# dashbutton_2450_v3.net
KiCad netlist of a schematic drawn in EAGLE
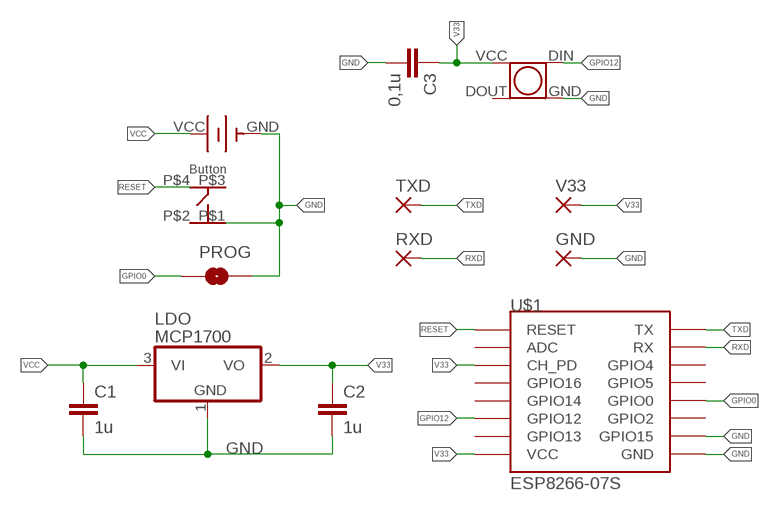
[diagram p0: schematic, sheet 1]

(export (version "E")
  (design (tool "Eeschema 10.0.6"))
  (components
    (comp (ref "BUTTON")
      (value "OMRON_B3FS_BUTTON")
      (footprint "eagle-import:BUTTON_OMRON_B3FS")
      (libsource (lib "eagle-import") (part "OMRON_B3FS_BUTTON"))
    )
    (comp (ref "C1")
      (value "1u")
      (footprint "eagle-import:C1206")
      (libsource (lib "eagle-import") (part "C-EUC1206"))
    )
    (comp (ref "C2")
      (value "1u")
      (footprint "eagle-import:C1206")
      (libsource (lib "eagle-import") (part "C-EUC1206"))
    )
    (comp (ref "C3")
      (value "0,1u")
      (footprint "eagle-import:C1206")
      (libsource (lib "eagle-import") (part "C-EUC1206"))
    )
    (comp (ref "GND")
      (value "WIREPADSMD1,27-254")
      (footprint "eagle-import:SMD1,27-2,54")
      (libsource (lib "eagle-import") (part "WIREPADSMD1,27-254"))
    )
    (comp (ref "LDO")
      (value "MCP1700")
      (footprint "eagle-import:SOT23")
      (libsource (lib "eagle-import") (part "MCP1703CB"))
    )
    (comp (ref "PROG")
      (value "JUMPER-SMT_2_NO_NO-SILK")
      (footprint "eagle-import:SMT-JUMPER_2_NO_NO-SILK")
      (libsource (lib "eagle-import") (part "JUMPER-SMT_2_NO_NO-SILK"))
    )
    (comp (ref "RXD")
      (value "WIREPADSMD1,27-254")
      (footprint "eagle-import:SMD1,27-2,54")
      (libsource (lib "eagle-import") (part "WIREPADSMD1,27-254"))
    )
    (comp (ref "TXD")
      (value "WIREPADSMD1,27-254")
      (footprint "eagle-import:SMD1,27-2,54")
      (libsource (lib "eagle-import") (part "WIREPADSMD1,27-254"))
    )
    (comp (ref "U$1")
      (value "ESP8266-07S")
      (footprint "eagle-import:ESP8266-07S")
      (libsource (lib "eagle-import") (part "ESP8266-07S"))
    )
    (comp (ref "U$2")
      (value "2450_BATTERYHOLDER_SMD")
      (footprint "eagle-import:2450_BATTERYHOLDER_SMD")
      (libsource (lib "eagle-import") (part "2450_BATTERYHOLDER_SMD"))
    )
    (comp (ref "U$3")
      (value "WS2812B")
      (footprint "eagle-import:WS2812B")
      (libsource (lib "eagle-import") (part "WS2812B"))
    )
    (comp (ref "V33")
      (value "WIREPADSMD1,27-254")
      (footprint "eagle-import:SMD1,27-2,54")
      (libsource (lib "eagle-import") (part "WIREPADSMD1,27-254"))
    )
  )
  (nets
    (net (code "1") (name "GND") (class "Default")
      (node (ref "BUTTON") (pin "P$1") (pinfunction "P1_P$1") (pintype "bidirectional"))
      (node (ref "C1") (pin "2") (pinfunction "2_2") (pintype "passive"))
      (node (ref "C2") (pin "2") (pinfunction "2_2") (pintype "passive"))
      (node (ref "C3") (pin "2") (pinfunction "2_2") (pintype "passive"))
      (node (ref "GND") (pin "1") (pinfunction "P_1") (pintype "passive"))
      (node (ref "LDO") (pin "1") (pinfunction "GND_1") (pintype "passive"))
      (node (ref "PROG") (pin "2") (pinfunction "2_2") (pintype "passive"))
      (node (ref "U$1") (pin "GND") (pinfunction "GND_GND") (pintype "bidirectional"))
      (node (ref "U$1") (pin "GPIO15") (pinfunction "GPIO15_GPIO15") (pintype "bidirectional"))
      (node (ref "U$2") (pin "GND") (pinfunction "GND_GND") (pintype "bidirectional"))
      (node (ref "U$3") (pin "GND") (pinfunction "GND_GND") (pintype "bidirectional"))
    )
    (net (code "2") (name "GPIO0") (class "Default")
      (node (ref "PROG") (pin "1") (pinfunction "1_1") (pintype "passive"))
      (node (ref "U$1") (pin "GPIO0") (pinfunction "GPIO0_GPIO0") (pintype "bidirectional"))
    )
    (net (code "3") (name "GPIO12") (class "Default")
      (node (ref "U$1") (pin "GPIO12") (pinfunction "GPIO12_GPIO12") (pintype "bidirectional"))
      (node (ref "U$3") (pin "DIN") (pinfunction "DIN_DIN") (pintype "bidirectional"))
    )
    (net (code "4") (name "RESET") (class "Default")
      (node (ref "BUTTON") (pin "P$4") (pinfunction "P4_P$4") (pintype "bidirectional"))
      (node (ref "U$1") (pin "RST") (pinfunction "RESET_RST") (pintype "bidirectional"))
    )
    (net (code "5") (name "RXD") (class "Default")
      (node (ref "RXD") (pin "1") (pinfunction "P_1") (pintype "passive"))
      (node (ref "U$1") (pin "RXD") (pinfunction "RX_RXD") (pintype "bidirectional"))
    )
    (net (code "6") (name "TXD") (class "Default")
      (node (ref "TXD") (pin "1") (pinfunction "P_1") (pintype "passive"))
      (node (ref "U$1") (pin "TXD") (pinfunction "TX_TXD") (pintype "bidirectional"))
    )
    (net (code "7") (name "V33") (class "Default")
      (node (ref "C2") (pin "1") (pinfunction "1_1") (pintype "passive"))
      (node (ref "C3") (pin "1") (pinfunction "1_1") (pintype "passive"))
      (node (ref "LDO") (pin "2") (pinfunction "VO_2") (pintype "passive"))
      (node (ref "U$1") (pin "EN") (pinfunction "CH_PD_EN") (pintype "bidirectional"))
      (node (ref "U$1") (pin "VCC") (pinfunction "VCC_VCC") (pintype "bidirectional"))
      (node (ref "U$3") (pin "VCC") (pinfunction "VCC_VCC") (pintype "bidirectional"))
      (node (ref "V33") (pin "1") (pinfunction "P_1") (pintype "passive"))
    )
    (net (code "8") (name "VCC") (class "Default")
      (node (ref "C1") (pin "1") (pinfunction "1_1") (pintype "passive"))
      (node (ref "LDO") (pin "3") (pinfunction "VI_3") (pintype "input"))
      (node (ref "U$2") (pin "VCC") (pinfunction "VCC_VCC") (pintype "bidirectional"))
    )
    (net (code "9") (name "unconnected-(BUTTON-P2-PadP$2)") (class "Default")
      (node (ref "BUTTON") (pin "P$2") (pinfunction "P2_P$2") (pintype "bidirectional"))
    )
    (net (code "10") (name "unconnected-(BUTTON-P3-PadP$3)") (class "Default")
      (node (ref "BUTTON") (pin "P$3") (pinfunction "P3_P$3") (pintype "bidirectional"))
    )
    (net (code "11") (name "unconnected-(U$1-PadADC)") (class "Default")
      (node (ref "U$1") (pin "ADC") (pinfunction "ADC_ADC") (pintype "bidirectional"))
    )
    (net (code "12") (name "unconnected-(U$1-PadGPIO2)") (class "Default")
      (node (ref "U$1") (pin "GPIO2") (pinfunction "GPIO2_GPIO2") (pintype "bidirectional"))
    )
    (net (code "13") (name "unconnected-(U$1-PadGPIO4)") (class "Default")
      (node (ref "U$1") (pin "GPIO4") (pinfunction "GPIO4_GPIO4") (pintype "bidirectional"))
    )
    (net (code "14") (name "unconnected-(U$1-PadGPIO5)") (class "Default")
      (node (ref "U$1") (pin "GPIO5") (pinfunction "GPIO5_GPIO5") (pintype "bidirectional"))
    )
    (net (code "15") (name "unconnected-(U$1-PadGPIO13)") (class "Default")
      (node (ref "U$1") (pin "GPIO13") (pinfunction "GPIO13_GPIO13") (pintype "bidirectional"))
    )
    (net (code "16") (name "unconnected-(U$1-PadGPIO14)") (class "Default")
      (node (ref "U$1") (pin "GPIO14") (pinfunction "GPIO14_GPIO14") (pintype "bidirectional"))
    )
    (net (code "17") (name "unconnected-(U$1-PadGPIO16)") (class "Default")
      (node (ref "U$1") (pin "GPIO16") (pinfunction "GPIO16_GPIO16") (pintype "bidirectional"))
    )
    (net (code "18") (name "unconnected-(U$3-PadDOUT)") (class "Default")
      (node (ref "U$3") (pin "DOUT") (pinfunction "DOUT_DOUT") (pintype "bidirectional"))
    )
  )
)
